# design.net
KiCad netlist of a schematic drawn in Altium Designer
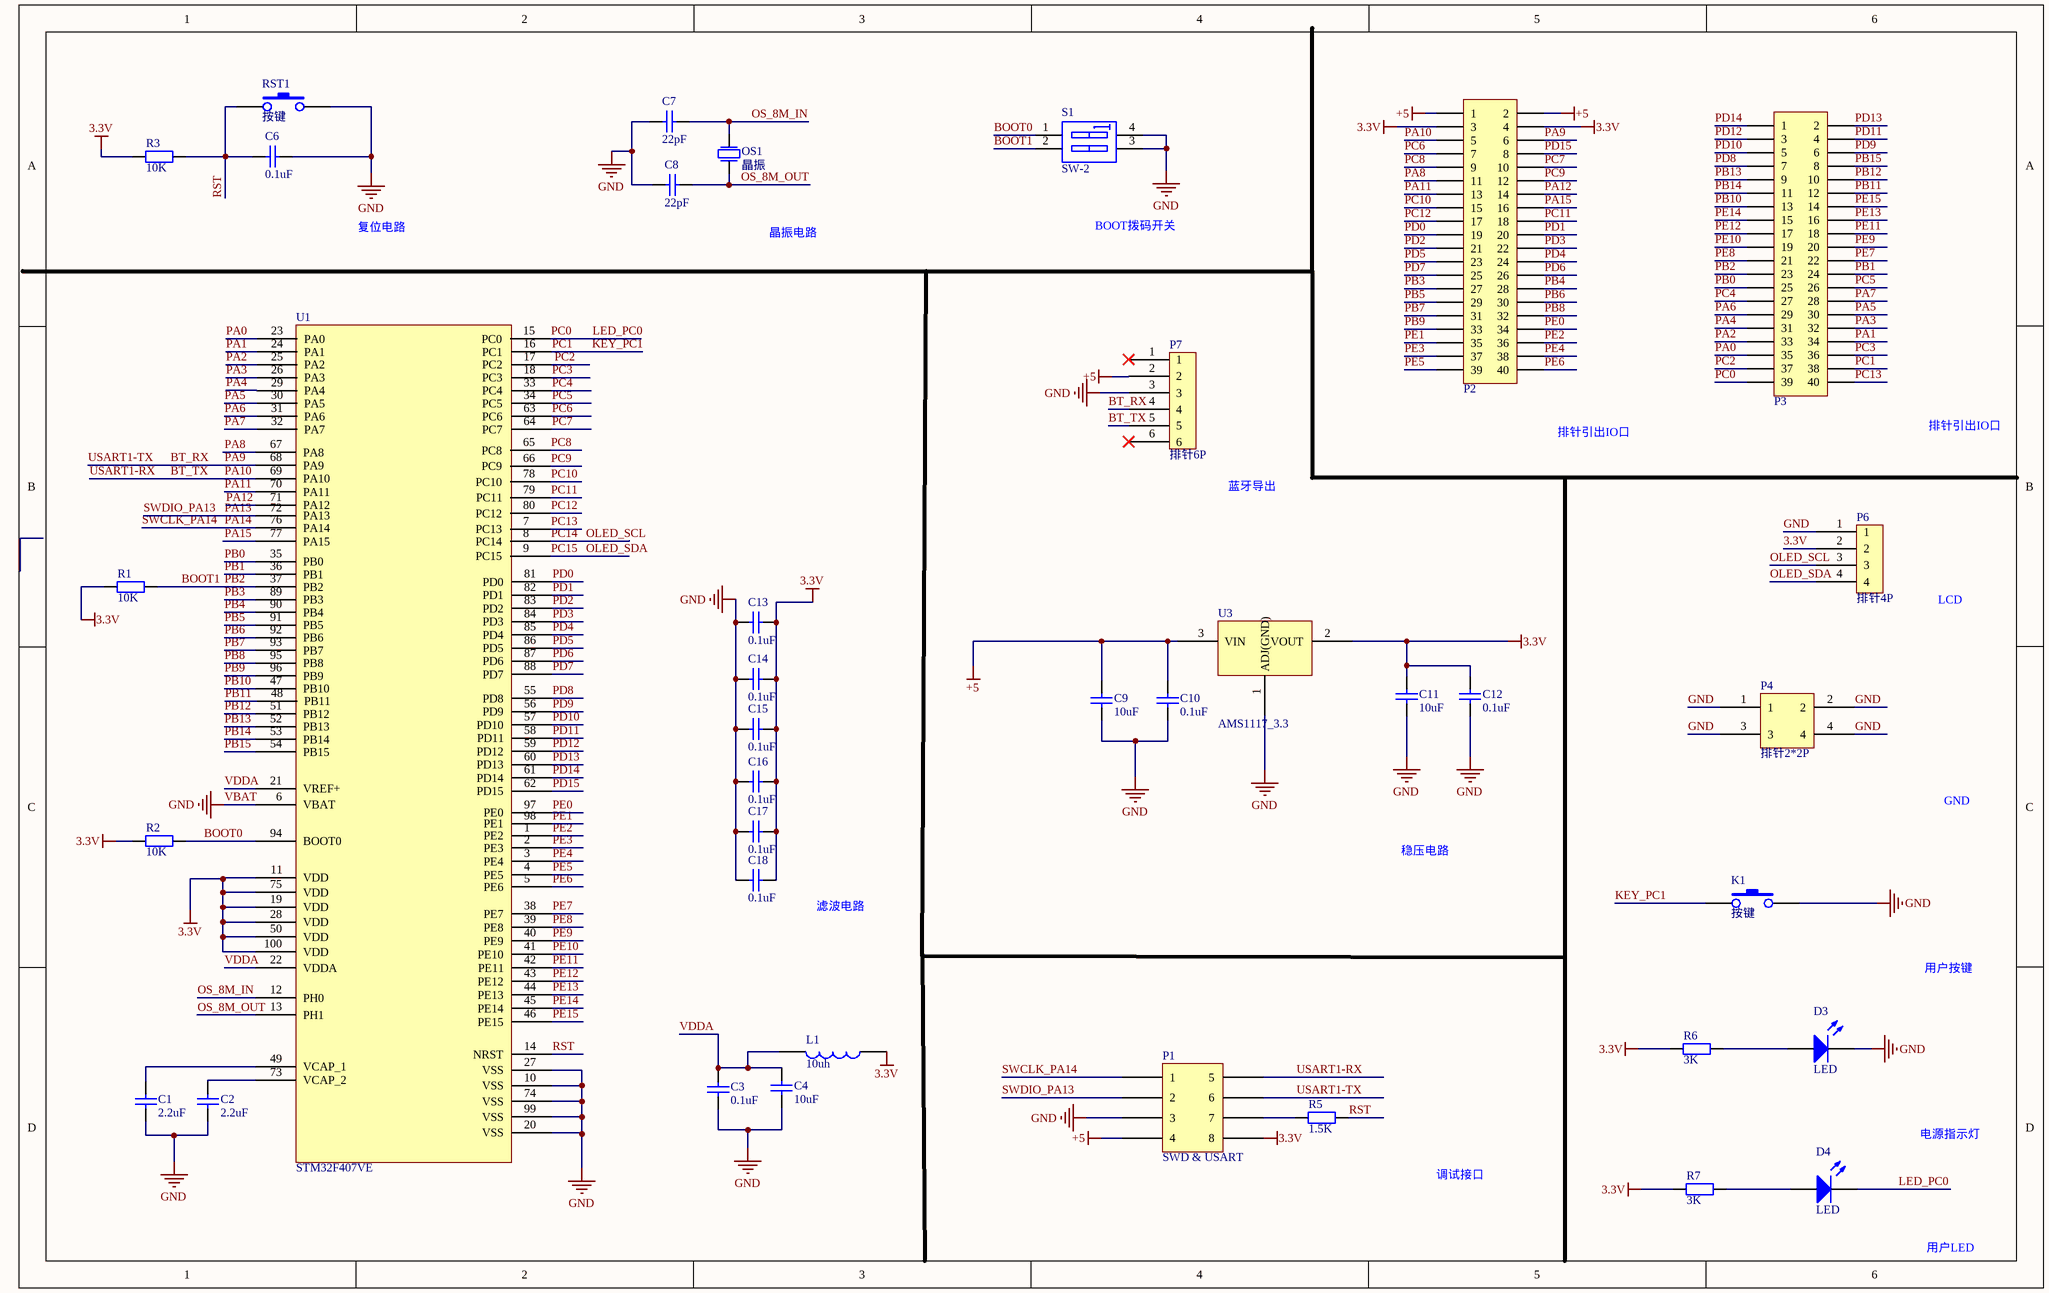
[diagram p0: 原理图.SchDoc]

(export (version "E")
  (design (tool "Eeschema 10.0.6"))
  (components
    (comp (ref "C1")
      (value "2.2uF")
      (footprint "0805_C")
      (description "电容")
      (libsource (lib "元件库") (part "CAP"))
    )
    (comp (ref "C2")
      (value "2.2uF")
      (footprint "0805_C")
      (description "电容")
      (libsource (lib "元件库") (part "CAP"))
    )
    (comp (ref "C3")
      (value "0.1uF")
      (footprint "0805_C")
      (description "电容")
      (libsource (lib "元件库") (part "CAP"))
    )
    (comp (ref "C4")
      (value "10uF")
      (footprint "0805_C")
      (description "电容")
      (libsource (lib "元件库") (part "CAP"))
    )
    (comp (ref "C6")
      (value "0.1uF")
      (footprint "0805_C")
      (description "电容")
      (libsource (lib "元件库") (part "CAP"))
    )
    (comp (ref "C7")
      (value "22pF")
      (footprint "0805_C")
      (description "电容")
      (libsource (lib "元件库") (part "CAP"))
    )
    (comp (ref "C8")
      (value "22pF")
      (footprint "0805_C")
      (description "电容")
      (libsource (lib "元件库") (part "CAP"))
    )
    (comp (ref "C9")
      (value "10uF")
      (footprint "0805_C")
      (description "电容")
      (libsource (lib "元件库") (part "CAP"))
    )
    (comp (ref "C10")
      (value "0.1uF")
      (footprint "0805_C")
      (description "电容")
      (libsource (lib "元件库") (part "CAP"))
    )
    (comp (ref "C11")
      (value "10uF")
      (footprint "0805_C")
      (description "电容")
      (libsource (lib "元件库") (part "CAP"))
    )
    (comp (ref "C12")
      (value "0.1uF")
      (footprint "0805_C")
      (description "电容")
      (libsource (lib "元件库") (part "CAP"))
    )
    (comp (ref "C13")
      (value "0.1uF")
      (footprint "0805_C")
      (description "电容")
      (libsource (lib "元件库") (part "CAP"))
    )
    (comp (ref "C14")
      (value "0.1uF")
      (footprint "0805_C")
      (description "电容")
      (libsource (lib "元件库") (part "CAP"))
    )
    (comp (ref "C15")
      (value "0.1uF")
      (footprint "0805_C")
      (description "电容")
      (libsource (lib "元件库") (part "CAP"))
    )
    (comp (ref "C16")
      (value "0.1uF")
      (footprint "0805_C")
      (description "电容")
      (libsource (lib "元件库") (part "CAP"))
    )
    (comp (ref "C17")
      (value "0.1uF")
      (footprint "0805_C")
      (description "电容")
      (libsource (lib "元件库") (part "CAP"))
    )
    (comp (ref "C18")
      (value "0.1uF")
      (footprint "0805_C")
      (description "电容")
      (libsource (lib "元件库") (part "CAP"))
    )
    (comp (ref "D3") (value "LED") (footprint "0805_L") (libsource (lib "元件库") (part "LED")))
    (comp (ref "D4") (value "LED") (footprint "0805_L") (libsource (lib "元件库") (part "LED")))
    (comp (ref "K1") (value "按键") (footprint "SWT3*4") (libsource (lib "元件库") (part "按键")))
    (comp (ref "L1") (value "10uh") (footprint "0805_I") (libsource (lib "元件库") (part "电感")))
    (comp (ref "OS1") (value "晶振") (footprint "5032_2P") (libsource (lib "元件库") (part "晶振")))
    (comp (ref "P1") (value "SWD & USART") (footprint "HDR2X4") (libsource (lib "元件库") (part "CON4-X2")))
    (comp (ref "P2") (value "排针2*40P") (footprint "HDR2X20") (libsource (lib "元件库") (part "排针2*40P")))
    (comp (ref "P3") (value "排针2*40P") (footprint "HDR2X20") (libsource (lib "元件库") (part "排针2*40P")))
    (comp (ref "P4") (value "排针2*2P") (footprint "HDR2X2") (libsource (lib "元件库") (part "排针2*2P")))
    (comp (ref "P6") (value "排针4P") (footprint "HDR4") (libsource (lib "元件库") (part "排针4P")))
    (comp (ref "P7") (value "排针6P") (footprint "HDR6") (libsource (lib "元件库") (part "排针6P")))
    (comp (ref "R1") (value "10K") (footprint "0805_R") (libsource (lib "元件库") (part "RES")))
    (comp (ref "R2") (value "10K") (footprint "0805_R") (libsource (lib "元件库") (part "RES")))
    (comp (ref "R3") (value "10K") (footprint "0805_R") (libsource (lib "元件库") (part "RES")))
    (comp (ref "R5") (value "1.5K") (footprint "0805_R") (libsource (lib "元件库") (part "RES")))
    (comp (ref "R6") (value "3K") (footprint "0805_R") (libsource (lib "元件库") (part "RES")))
    (comp (ref "R7") (value "3K") (footprint "0805_R") (libsource (lib "元件库") (part "RES")))
    (comp (ref "RST1") (value "按键") (footprint "SWT3*4") (libsource (lib "元件库") (part "按键")))
    (comp (ref "S1") (value "SW-2") (footprint "SWT10*6_P4") (libsource (lib "元件库") (part "SW-2")))
    (comp (ref "U1")
      (value "STM32F407VE")
      (footprint "QFP-100_14x14x05P")
      (description "IC")
      (libsource (lib "元件库") (part "STM32F407VE"))
    )
    (comp (ref "U3") (value "AMS1117_3.3") (footprint "SOT-223") (libsource (lib "元件库") (part "AMS1117_3.3")))
  )
  (nets
    (net (code "1") (name "+5") (class "Default")
      (node (ref "C10") (pin "2") (pinfunction "2_2") (pintype "passive"))
      (node (ref "C9") (pin "1") (pinfunction "1_1") (pintype "passive"))
      (node (ref "P1") (pin "4") (pinfunction "4_4") (pintype "passive"))
      (node (ref "P2") (pin "1") (pinfunction "1_1") (pintype "passive"))
      (node (ref "P2") (pin "2") (pinfunction "2_2") (pintype "passive"))
      (node (ref "P7") (pin "2") (pinfunction "2_2") (pintype "passive"))
      (node (ref "U3") (pin "3") (pinfunction "VIN_3") (pintype "passive"))
    )
    (net (code "2") (name "/BOOT0") (class "Default")
      (node (ref "R2") (pin "2") (pinfunction "2_2") (pintype "passive"))
      (node (ref "S1") (pin "1") (pinfunction "A1_1") (pintype "passive"))
      (node (ref "U1") (pin "94") (pinfunction "BOOT0_94") (pintype "passive"))
    )
    (net (code "3") (name "/BOOT1") (class "Default")
      (node (ref "P3") (pin "23") (pinfunction "23_23") (pintype "passive"))
      (node (ref "R1") (pin "2") (pinfunction "2_2") (pintype "passive"))
      (node (ref "S1") (pin "2") (pinfunction "A2_2") (pintype "passive"))
      (node (ref "U1") (pin "37") (pinfunction "PB2_37") (pintype "passive"))
    )
    (net (code "4") (name "/BT_RX") (class "Default")
      (node (ref "P1") (pin "6") (pinfunction "6_6") (pintype "passive"))
      (node (ref "P2") (pin "6") (pinfunction "6_6") (pintype "passive"))
      (node (ref "P7") (pin "4") (pinfunction "4_4") (pintype "passive"))
      (node (ref "U1") (pin "68") (pinfunction "PA9_68") (pintype "passive"))
    )
    (net (code "5") (name "/BT_TX") (class "Default")
      (node (ref "P1") (pin "5") (pinfunction "5_5") (pintype "passive"))
      (node (ref "P2") (pin "5") (pinfunction "5_5") (pintype "passive"))
      (node (ref "P7") (pin "5") (pinfunction "5_5") (pintype "passive"))
      (node (ref "U1") (pin "69") (pinfunction "PA10_69") (pintype "passive"))
    )
    (net (code "6") (name "/KEY_PC1") (class "Default")
      (node (ref "K1") (pin "1") (pinfunction "1_1") (pintype "passive"))
      (node (ref "P3") (pin "38") (pinfunction "38_38") (pintype "passive"))
      (node (ref "U1") (pin "16") (pinfunction "PC1_16") (pintype "passive"))
    )
    (net (code "7") (name "/LED_PC0") (class "Default")
      (node (ref "D4") (pin "2") (pinfunction "K_2") (pintype "passive"))
      (node (ref "P3") (pin "39") (pinfunction "39_39") (pintype "passive"))
      (node (ref "U1") (pin "15") (pinfunction "PC0_15") (pintype "passive"))
    )
    (net (code "8") (name "/OLED_SCL") (class "Default")
      (node (ref "P6") (pin "3") (pinfunction "3_3") (pintype "passive"))
      (node (ref "U1") (pin "8") (pinfunction "PC14_8") (pintype "passive"))
    )
    (net (code "9") (name "/OLED_SDA") (class "Default")
      (node (ref "P6") (pin "4") (pinfunction "4_4") (pintype "passive"))
      (node (ref "U1") (pin "9") (pinfunction "PC15_9") (pintype "passive"))
    )
    (net (code "10") (name "/OS_8M_IN") (class "Default")
      (node (ref "C7") (pin "2") (pinfunction "2_2") (pintype "passive"))
      (node (ref "OS1") (pin "1") (pinfunction "P1_1") (pintype "passive"))
      (node (ref "U1") (pin "12") (pinfunction "PH0_12") (pintype "passive"))
    )
    (net (code "11") (name "/OS_8M_OUT") (class "Default")
      (node (ref "C8") (pin "2") (pinfunction "2_2") (pintype "passive"))
      (node (ref "OS1") (pin "2") (pinfunction "P2_2") (pintype "passive"))
      (node (ref "U1") (pin "13") (pinfunction "PH1_13") (pintype "passive"))
    )
    (net (code "12") (name "/PA0") (class "Default")
      (node (ref "P3") (pin "35") (pinfunction "35_35") (pintype "passive"))
      (node (ref "U1") (pin "23") (pinfunction "PA0_23") (pintype "passive"))
    )
    (net (code "13") (name "/PA1") (class "Default")
      (node (ref "P3") (pin "34") (pinfunction "34_34") (pintype "passive"))
      (node (ref "U1") (pin "24") (pinfunction "PA1_24") (pintype "passive"))
    )
    (net (code "14") (name "/PA2") (class "Default")
      (node (ref "P3") (pin "33") (pinfunction "33_33") (pintype "passive"))
      (node (ref "U1") (pin "25") (pinfunction "PA2_25") (pintype "passive"))
    )
    (net (code "15") (name "/PA3") (class "Default")
      (node (ref "P3") (pin "32") (pinfunction "32_32") (pintype "passive"))
      (node (ref "U1") (pin "26") (pinfunction "PA3_26") (pintype "passive"))
    )
    (net (code "16") (name "/PA4") (class "Default")
      (node (ref "P3") (pin "31") (pinfunction "31_31") (pintype "passive"))
      (node (ref "U1") (pin "29") (pinfunction "PA4_29") (pintype "passive"))
    )
    (net (code "17") (name "/PA5") (class "Default")
      (node (ref "P3") (pin "30") (pinfunction "30_30") (pintype "passive"))
      (node (ref "U1") (pin "30") (pinfunction "PA5_30") (pintype "passive"))
    )
    (net (code "18") (name "/PA6") (class "Default")
      (node (ref "P3") (pin "29") (pinfunction "29_29") (pintype "passive"))
      (node (ref "U1") (pin "31") (pinfunction "PA6_31") (pintype "passive"))
    )
    (net (code "19") (name "/PA7") (class "Default")
      (node (ref "P3") (pin "28") (pinfunction "28_28") (pintype "passive"))
      (node (ref "U1") (pin "32") (pinfunction "PA7_32") (pintype "passive"))
    )
    (net (code "20") (name "/PA8") (class "Default")
      (node (ref "P2") (pin "11") (pinfunction "11_11") (pintype "passive"))
      (node (ref "U1") (pin "67") (pinfunction "PA8_67") (pintype "passive"))
    )
    (net (code "21") (name "/PA11") (class "Default")
      (node (ref "P2") (pin "13") (pinfunction "13_13") (pintype "passive"))
      (node (ref "U1") (pin "70") (pinfunction "PA11_70") (pintype "passive"))
    )
    (net (code "22") (name "/PA12") (class "Default")
      (node (ref "P2") (pin "14") (pinfunction "14_14") (pintype "passive"))
      (node (ref "U1") (pin "71") (pinfunction "PA12_71") (pintype "passive"))
    )
    (net (code "23") (name "/PA13") (class "Default")
      (node (ref "P1") (pin "2") (pinfunction "2_2") (pintype "passive"))
      (node (ref "U1") (pin "72") (pinfunction "PA13_72") (pintype "passive"))
    )
    (net (code "24") (name "/PA14") (class "Default")
      (node (ref "P1") (pin "1") (pinfunction "1_1") (pintype "passive"))
      (node (ref "U1") (pin "76") (pinfunction "PA14_76") (pintype "passive"))
    )
    (net (code "25") (name "/PA15") (class "Default")
      (node (ref "P2") (pin "16") (pinfunction "16_16") (pintype "passive"))
      (node (ref "U1") (pin "77") (pinfunction "PA15_77") (pintype "passive"))
    )
    (net (code "26") (name "/PB0") (class "Default")
      (node (ref "P3") (pin "25") (pinfunction "25_25") (pintype "passive"))
      (node (ref "U1") (pin "35") (pinfunction "PB0_35") (pintype "passive"))
    )
    (net (code "27") (name "/PB1") (class "Default")
      (node (ref "P3") (pin "24") (pinfunction "24_24") (pintype "passive"))
      (node (ref "U1") (pin "36") (pinfunction "PB1_36") (pintype "passive"))
    )
    (net (code "28") (name "/PB3") (class "Default")
      (node (ref "P2") (pin "27") (pinfunction "27_27") (pintype "passive"))
      (node (ref "U1") (pin "89") (pinfunction "PB3_89") (pintype "passive"))
    )
    (net (code "29") (name "/PB4") (class "Default")
      (node (ref "P2") (pin "28") (pinfunction "28_28") (pintype "passive"))
      (node (ref "U1") (pin "90") (pinfunction "PB4_90") (pintype "passive"))
    )
    (net (code "30") (name "/PB5") (class "Default")
      (node (ref "P2") (pin "29") (pinfunction "29_29") (pintype "passive"))
      (node (ref "U1") (pin "91") (pinfunction "PB5_91") (pintype "passive"))
    )
    (net (code "31") (name "/PB6") (class "Default")
      (node (ref "P2") (pin "30") (pinfunction "30_30") (pintype "passive"))
      (node (ref "U1") (pin "92") (pinfunction "PB6_92") (pintype "passive"))
    )
    (net (code "32") (name "/PB7") (class "Default")
      (node (ref "P2") (pin "31") (pinfunction "31_31") (pintype "passive"))
      (node (ref "U1") (pin "93") (pinfunction "PB7_93") (pintype "passive"))
    )
    (net (code "33") (name "/PB8") (class "Default")
      (node (ref "P2") (pin "32") (pinfunction "32_32") (pintype "passive"))
      (node (ref "U1") (pin "95") (pinfunction "PB8_95") (pintype "passive"))
    )
    (net (code "34") (name "/PB9") (class "Default")
      (node (ref "P2") (pin "33") (pinfunction "33_33") (pintype "passive"))
      (node (ref "U1") (pin "96") (pinfunction "PB9_96") (pintype "passive"))
    )
    (net (code "35") (name "/PB10") (class "Default")
      (node (ref "P3") (pin "13") (pinfunction "13_13") (pintype "passive"))
      (node (ref "U1") (pin "47") (pinfunction "PB10_47") (pintype "passive"))
    )
    (net (code "36") (name "/PB11") (class "Default")
      (node (ref "P3") (pin "12") (pinfunction "12_12") (pintype "passive"))
      (node (ref "U1") (pin "48") (pinfunction "PB11_48") (pintype "passive"))
    )
    (net (code "37") (name "/PB12") (class "Default")
      (node (ref "P3") (pin "10") (pinfunction "10_10") (pintype "passive"))
      (node (ref "U1") (pin "51") (pinfunction "PB12_51") (pintype "passive"))
    )
    (net (code "38") (name "/PB13") (class "Default")
      (node (ref "P3") (pin "9") (pinfunction "9_9") (pintype "passive"))
      (node (ref "U1") (pin "52") (pinfunction "PB13_52") (pintype "passive"))
    )
    (net (code "39") (name "/PB14") (class "Default")
      (node (ref "P3") (pin "11") (pinfunction "11_11") (pintype "passive"))
      (node (ref "U1") (pin "53") (pinfunction "PB14_53") (pintype "passive"))
    )
    (net (code "40") (name "/PB15") (class "Default")
      (node (ref "P3") (pin "8") (pinfunction "8_8") (pintype "passive"))
      (node (ref "U1") (pin "54") (pinfunction "PB15_54") (pintype "passive"))
    )
    (net (code "41") (name "/PC2") (class "Default")
      (node (ref "P3") (pin "37") (pinfunction "37_37") (pintype "passive"))
      (node (ref "U1") (pin "17") (pinfunction "PC2_17") (pintype "passive"))
    )
    (net (code "42") (name "/PC3") (class "Default")
      (node (ref "P3") (pin "36") (pinfunction "36_36") (pintype "passive"))
      (node (ref "U1") (pin "18") (pinfunction "PC3_18") (pintype "passive"))
    )
    (net (code "43") (name "/PC4") (class "Default")
      (node (ref "P3") (pin "27") (pinfunction "27_27") (pintype "passive"))
      (node (ref "U1") (pin "33") (pinfunction "PC4_33") (pintype "passive"))
    )
    (net (code "44") (name "/PC5") (class "Default")
      (node (ref "P3") (pin "26") (pinfunction "26_26") (pintype "passive"))
      (node (ref "U1") (pin "34") (pinfunction "PC5_34") (pintype "passive"))
    )
    (net (code "45") (name "/PC6") (class "Default")
      (node (ref "P2") (pin "7") (pinfunction "7_7") (pintype "passive"))
      (node (ref "U1") (pin "63") (pinfunction "PC6_63") (pintype "passive"))
    )
    (net (code "46") (name "/PC7") (class "Default")
      (node (ref "P2") (pin "10") (pinfunction "10_10") (pintype "passive"))
      (node (ref "U1") (pin "64") (pinfunction "PC7_64") (pintype "passive"))
    )
    (net (code "47") (name "/PC8") (class "Default")
      (node (ref "P2") (pin "9") (pinfunction "9_9") (pintype "passive"))
      (node (ref "U1") (pin "65") (pinfunction "PC8_65") (pintype "passive"))
    )
    (net (code "48") (name "/PC9") (class "Default")
      (node (ref "P2") (pin "12") (pinfunction "12_12") (pintype "passive"))
      (node (ref "U1") (pin "66") (pinfunction "PC9_66") (pintype "passive"))
    )
    (net (code "49") (name "/PC10") (class "Default")
      (node (ref "P2") (pin "15") (pinfunction "15_15") (pintype "passive"))
      (node (ref "U1") (pin "78") (pinfunction "PC10_78") (pintype "passive"))
    )
    (net (code "50") (name "/PC11") (class "Default")
      (node (ref "P2") (pin "18") (pinfunction "18_18") (pintype "passive"))
      (node (ref "U1") (pin "79") (pinfunction "PC11_79") (pintype "passive"))
    )
    (net (code "51") (name "/PC12") (class "Default")
      (node (ref "P2") (pin "17") (pinfunction "17_17") (pintype "passive"))
      (node (ref "U1") (pin "80") (pinfunction "PC12_80") (pintype "passive"))
    )
    (net (code "52") (name "/PC13") (class "Default")
      (node (ref "P3") (pin "40") (pinfunction "40_40") (pintype "passive"))
      (node (ref "U1") (pin "7") (pinfunction "PC13_7") (pintype "passive"))
    )
    (net (code "53") (name "/PD0") (class "Default")
      (node (ref "P2") (pin "19") (pinfunction "19_19") (pintype "passive"))
      (node (ref "U1") (pin "81") (pinfunction "PD0_81") (pintype "passive"))
    )
    (net (code "54") (name "/PD1") (class "Default")
      (node (ref "P2") (pin "20") (pinfunction "20_20") (pintype "passive"))
      (node (ref "U1") (pin "82") (pinfunction "PD1_82") (pintype "passive"))
    )
    (net (code "55") (name "/PD2") (class "Default")
      (node (ref "P2") (pin "21") (pinfunction "21_21") (pintype "passive"))
      (node (ref "U1") (pin "83") (pinfunction "PD2_83") (pintype "passive"))
    )
    (net (code "56") (name "/PD3") (class "Default")
      (node (ref "P2") (pin "22") (pinfunction "22_22") (pintype "passive"))
      (node (ref "U1") (pin "84") (pinfunction "PD3_84") (pintype "passive"))
    )
    (net (code "57") (name "/PD4") (class "Default")
      (node (ref "P2") (pin "24") (pinfunction "24_24") (pintype "passive"))
      (node (ref "U1") (pin "85") (pinfunction "PD4_85") (pintype "passive"))
    )
    (net (code "58") (name "/PD5") (class "Default")
      (node (ref "P2") (pin "23") (pinfunction "23_23") (pintype "passive"))
      (node (ref "U1") (pin "86") (pinfunction "PD5_86") (pintype "passive"))
    )
    (net (code "59") (name "/PD6") (class "Default")
      (node (ref "P2") (pin "26") (pinfunction "26_26") (pintype "passive"))
      (node (ref "U1") (pin "87") (pinfunction "PD6_87") (pintype "passive"))
    )
    (net (code "60") (name "/PD7") (class "Default")
      (node (ref "P2") (pin "25") (pinfunction "25_25") (pintype "passive"))
      (node (ref "U1") (pin "88") (pinfunction "PD7_88") (pintype "passive"))
    )
    (net (code "61") (name "/PD8") (class "Default")
      (node (ref "P3") (pin "7") (pinfunction "7_7") (pintype "passive"))
      (node (ref "U1") (pin "55") (pinfunction "PD8_55") (pintype "passive"))
    )
    (net (code "62") (name "/PD9") (class "Default")
      (node (ref "P3") (pin "6") (pinfunction "6_6") (pintype "passive"))
      (node (ref "U1") (pin "56") (pinfunction "PD9_56") (pintype "passive"))
    )
    (net (code "63") (name "/PD10") (class "Default")
      (node (ref "P3") (pin "5") (pinfunction "5_5") (pintype "passive"))
      (node (ref "U1") (pin "57") (pinfunction "PD10_57") (pintype "passive"))
    )
    (net (code "64") (name "/PD11") (class "Default")
      (node (ref "P3") (pin "4") (pinfunction "4_4") (pintype "passive"))
      (node (ref "U1") (pin "58") (pinfunction "PD11_58") (pintype "passive"))
    )
    (net (code "65") (name "/PD12") (class "Default")
      (node (ref "P3") (pin "3") (pinfunction "3_3") (pintype "passive"))
      (node (ref "U1") (pin "59") (pinfunction "PD12_59") (pintype "passive"))
    )
    (net (code "66") (name "/PD13") (class "Default")
      (node (ref "P3") (pin "2") (pinfunction "2_2") (pintype "passive"))
      (node (ref "U1") (pin "60") (pinfunction "PD13_60") (pintype "passive"))
    )
    (net (code "67") (name "/PD14") (class "Default")
      (node (ref "P3") (pin "1") (pinfunction "1_1") (pintype "passive"))
      (node (ref "U1") (pin "61") (pinfunction "PD14_61") (pintype "passive"))
    )
    (net (code "68") (name "/PD15") (class "Default")
      (node (ref "P2") (pin "8") (pinfunction "8_8") (pintype "passive"))
      (node (ref "U1") (pin "62") (pinfunction "PD15_62") (pintype "passive"))
    )
    (net (code "69") (name "/PE0") (class "Default")
      (node (ref "P2") (pin "34") (pinfunction "34_34") (pintype "passive"))
      (node (ref "U1") (pin "97") (pinfunction "PE0_97") (pintype "passive"))
    )
    (net (code "70") (name "/PE1") (class "Default")
      (node (ref "P2") (pin "35") (pinfunction "35_35") (pintype "passive"))
      (node (ref "U1") (pin "98") (pinfunction "PE1_98") (pintype "passive"))
    )
    (net (code "71") (name "/PE2") (class "Default")
      (node (ref "P2") (pin "36") (pinfunction "36_36") (pintype "passive"))
      (node (ref "U1") (pin "1") (pinfunction "PE2_1") (pintype "passive"))
    )
    (net (code "72") (name "/PE3") (class "Default")
      (node (ref "P2") (pin "37") (pinfunction "37_37") (pintype "passive"))
      (node (ref "U1") (pin "2") (pinfunction "PE3_2") (pintype "passive"))
    )
    (net (code "73") (name "/PE4") (class "Default")
      (node (ref "P2") (pin "38") (pinfunction "38_38") (pintype "passive"))
      (node (ref "U1") (pin "3") (pinfunction "PE4_3") (pintype "passive"))
    )
    (net (code "74") (name "/PE5") (class "Default")
      (node (ref "P2") (pin "39") (pinfunction "39_39") (pintype "passive"))
      (node (ref "U1") (pin "4") (pinfunction "PE5_4") (pintype "passive"))
    )
    (net (code "75") (name "/PE6") (class "Default")
      (node (ref "P2") (pin "40") (pinfunction "40_40") (pintype "passive"))
      (node (ref "U1") (pin "5") (pinfunction "PE6_5") (pintype "passive"))
    )
    (net (code "76") (name "/PE7") (class "Default")
      (node (ref "P3") (pin "22") (pinfunction "22_22") (pintype "passive"))
      (node (ref "U1") (pin "38") (pinfunction "PE7_38") (pintype "passive"))
    )
    (net (code "77") (name "/PE8") (class "Default")
      (node (ref "P3") (pin "21") (pinfunction "21_21") (pintype "passive"))
      (node (ref "U1") (pin "39") (pinfunction "PE8_39") (pintype "passive"))
    )
    (net (code "78") (name "/PE9") (class "Default")
      (node (ref "P3") (pin "20") (pinfunction "20_20") (pintype "passive"))
      (node (ref "U1") (pin "40") (pinfunction "PE9_40") (pintype "passive"))
    )
    (net (code "79") (name "/PE10") (class "Default")
      (node (ref "P3") (pin "19") (pinfunction "19_19") (pintype "passive"))
      (node (ref "U1") (pin "41") (pinfunction "PE10_41") (pintype "passive"))
    )
    (net (code "80") (name "/PE11") (class "Default")
      (node (ref "P3") (pin "18") (pinfunction "18_18") (pintype "passive"))
      (node (ref "U1") (pin "42") (pinfunction "PE11_42") (pintype "passive"))
    )
    (net (code "81") (name "/PE12") (class "Default")
      (node (ref "P3") (pin "17") (pinfunction "17_17") (pintype "passive"))
      (node (ref "U1") (pin "43") (pinfunction "PE12_43") (pintype "passive"))
    )
    (net (code "82") (name "/PE13") (class "Default")
      (node (ref "P3") (pin "16") (pinfunction "16_16") (pintype "passive"))
      (node (ref "U1") (pin "44") (pinfunction "PE13_44") (pintype "passive"))
    )
    (net (code "83") (name "/PE14") (class "Default")
      (node (ref "P3") (pin "15") (pinfunction "15_15") (pintype "passive"))
      (node (ref "U1") (pin "45") (pinfunction "PE14_45") (pintype "passive"))
    )
    (net (code "84") (name "/PE15") (class "Default")
      (node (ref "P3") (pin "14") (pinfunction "14_14") (pintype "passive"))
      (node (ref "U1") (pin "46") (pinfunction "PE15_46") (pintype "passive"))
    )
    (net (code "85") (name "/RST") (class "Default")
      (node (ref "C6") (pin "1") (pinfunction "1_1") (pintype "passive"))
      (node (ref "R3") (pin "2") (pinfunction "2_2") (pintype "passive"))
      (node (ref "R5") (pin "2") (pinfunction "2_2") (pintype "passive"))
      (node (ref "RST1") (pin "1") (pinfunction "1_1") (pintype "passive"))
      (node (ref "U1") (pin "14") (pinfunction "NRST_14") (pintype "passive"))
    )
    (net (code "86") (name "/VDDA") (class "Default")
      (node (ref "C3") (pin "2") (pinfunction "2_2") (pintype "passive"))
      (node (ref "C4") (pin "1") (pinfunction "1_1") (pintype "passive"))
      (node (ref "L1") (pin "2") (pinfunction "2_2") (pintype "passive"))
      (node (ref "U1") (pin "21") (pinfunction "VREF+_21") (pintype "passive"))
      (node (ref "U1") (pin "22") (pinfunction "VDDA_22") (pintype "passive"))
    )
    (net (code "87") (name "3.3V") (class "Default")
      (node (ref "C11") (pin "2") (pinfunction "2_2") (pintype "passive"))
      (node (ref "C12") (pin "1") (pinfunction "1_1") (pintype "passive"))
      (node (ref "C13") (pin "1") (pinfunction "1_1") (pintype "passive"))
      (node (ref "C14") (pin "1") (pinfunction "1_1") (pintype "passive"))
      (node (ref "C15") (pin "1") (pinfunction "1_1") (pintype "passive"))
      (node (ref "C16") (pin "1") (pinfunction "1_1") (pintype "passive"))
      (node (ref "C17") (pin "1") (pinfunction "1_1") (pintype "passive"))
      (node (ref "C18") (pin "1") (pinfunction "1_1") (pintype "passive"))
      (node (ref "L1") (pin "1") (pinfunction "1_1") (pintype "passive"))
      (node (ref "P1") (pin "8") (pinfunction "8_8") (pintype "passive"))
      (node (ref "P2") (pin "3") (pinfunction "3_3") (pintype "passive"))
      (node (ref "P2") (pin "4") (pinfunction "4_4") (pintype "passive"))
      (node (ref "P6") (pin "2") (pinfunction "2_2") (pintype "passive"))
      (node (ref "R1") (pin "1") (pinfunction "1_1") (pintype "passive"))
      (node (ref "R2") (pin "1") (pinfunction "1_1") (pintype "passive"))
      (node (ref "R3") (pin "1") (pinfunction "1_1") (pintype "passive"))
      (node (ref "R6") (pin "1") (pinfunction "1_1") (pintype "passive"))
      (node (ref "R7") (pin "1") (pinfunction "1_1") (pintype "passive"))
      (node (ref "U1") (pin "100") (pinfunction "VDD_100") (pintype "passive"))
      (node (ref "U1") (pin "11") (pinfunction "VDD_11") (pintype "passive"))
      (node (ref "U1") (pin "19") (pinfunction "VDD_19") (pintype "passive"))
      (node (ref "U1") (pin "28") (pinfunction "VDD_28") (pintype "passive"))
      (node (ref "U1") (pin "50") (pinfunction "VDD_50") (pintype "passive"))
      (node (ref "U1") (pin "75") (pinfunction "VDD_75") (pintype "passive"))
      (node (ref "U3") (pin "2") (pinfunction "VOUT_2") (pintype "passive"))
    )
    (net (code "88") (name "GND") (class "Default")
      (node (ref "C1") (pin "1") (pinfunction "1_1") (pintype "passive"))
      (node (ref "C10") (pin "1") (pinfunction "1_1") (pintype "passive"))
      (node (ref "C11") (pin "1") (pinfunction "1_1") (pintype "passive"))
      (node (ref "C12") (pin "2") (pinfunction "2_2") (pintype "passive"))
      (node (ref "C13") (pin "2") (pinfunction "2_2") (pintype "passive"))
      (node (ref "C14") (pin "2") (pinfunction "2_2") (pintype "passive"))
      (node (ref "C15") (pin "2") (pinfunction "2_2") (pintype "passive"))
      (node (ref "C16") (pin "2") (pinfunction "2_2") (pintype "passive"))
      (node (ref "C17") (pin "2") (pinfunction "2_2") (pintype "passive"))
      (node (ref "C18") (pin "2") (pinfunction "2_2") (pintype "passive"))
      (node (ref "C2") (pin "1") (pinfunction "1_1") (pintype "passive"))
      (node (ref "C3") (pin "1") (pinfunction "1_1") (pintype "passive"))
      (node (ref "C4") (pin "2") (pinfunction "2_2") (pintype "passive"))
      (node (ref "C6") (pin "2") (pinfunction "2_2") (pintype "passive"))
      (node (ref "C7") (pin "1") (pinfunction "1_1") (pintype "passive"))
      (node (ref "C8") (pin "1") (pinfunction "1_1") (pintype "passive"))
      (node (ref "C9") (pin "2") (pinfunction "2_2") (pintype "passive"))
      (node (ref "D3") (pin "2") (pinfunction "K_2") (pintype "passive"))
      (node (ref "K1") (pin "2") (pinfunction "2_2") (pintype "passive"))
      (node (ref "P1") (pin "3") (pinfunction "3_3") (pintype "passive"))
      (node (ref "P4") (pin "1") (pinfunction "1_1") (pintype "passive"))
      (node (ref "P4") (pin "2") (pinfunction "2_2") (pintype "passive"))
      (node (ref "P4") (pin "3") (pinfunction "3_3") (pintype "passive"))
      (node (ref "P4") (pin "4") (pinfunction "4_4") (pintype "passive"))
      (node (ref "P6") (pin "1") (pinfunction "1_1") (pintype "passive"))
      (node (ref "P7") (pin "3") (pinfunction "3_3") (pintype "passive"))
      (node (ref "RST1") (pin "2") (pinfunction "2_2") (pintype "passive"))
      (node (ref "S1") (pin "3") (pinfunction "B2_3") (pintype "passive"))
      (node (ref "S1") (pin "4") (pinfunction "B1_4") (pintype "passive"))
      (node (ref "U1") (pin "10") (pinfunction "VSS_10") (pintype "passive"))
      (node (ref "U1") (pin "20") (pinfunction "VSS_20") (pintype "passive"))
      (node (ref "U1") (pin "27") (pinfunction "VSS_27") (pintype "passive"))
      (node (ref "U1") (pin "6") (pinfunction "VBAT_6") (pintype "passive"))
      (node (ref "U1") (pin "74") (pinfunction "VSS_74") (pintype "passive"))
      (node (ref "U1") (pin "99") (pinfunction "VSS_99") (pintype "passive"))
      (node (ref "U3") (pin "1") (pinfunction "ADJ(GND)_1") (pintype "passive"))
    )
    (net (code "89") (name "Net-(D3-A)") (class "Default")
      (node (ref "D3") (pin "1") (pinfunction "A_1") (pintype "passive"))
      (node (ref "R6") (pin "2") (pinfunction "2_2") (pintype "passive"))
    )
    (net (code "90") (name "Net-(D4-A)") (class "Default")
      (node (ref "D4") (pin "1") (pinfunction "A_1") (pintype "passive"))
      (node (ref "R7") (pin "2") (pinfunction "2_2") (pintype "passive"))
    )
    (net (code "91") (name "Net-(P1-Pad7)") (class "Default")
      (node (ref "P1") (pin "7") (pinfunction "7_7") (pintype "passive"))
      (node (ref "R5") (pin "1") (pinfunction "1_1") (pintype "passive"))
    )
    (net (code "92") (name "Net-(U1-VCAP_1)") (class "Default")
      (node (ref "C1") (pin "2") (pinfunction "2_2") (pintype "passive"))
      (node (ref "U1") (pin "49") (pinfunction "VCAP_1_49") (pintype "passive"))
    )
    (net (code "93") (name "Net-(U1-VCAP_2)") (class "Default")
      (node (ref "C2") (pin "2") (pinfunction "2_2") (pintype "passive"))
      (node (ref "U1") (pin "73") (pinfunction "VCAP_2_73") (pintype "passive"))
    )
    (net (code "94") (name "unconnected-(P7-Pad1)") (class "Default")
      (node (ref "P7") (pin "1") (pinfunction "1_1") (pintype "passive+no_connect"))
    )
    (net (code "95") (name "unconnected-(P7-Pad6)") (class "Default")
      (node (ref "P7") (pin "6") (pinfunction "6_6") (pintype "passive+no_connect"))
    )
  )
)
